# OpenC4D_Shield-version2.net
KiCad netlist of a schematic drawn in EAGLE
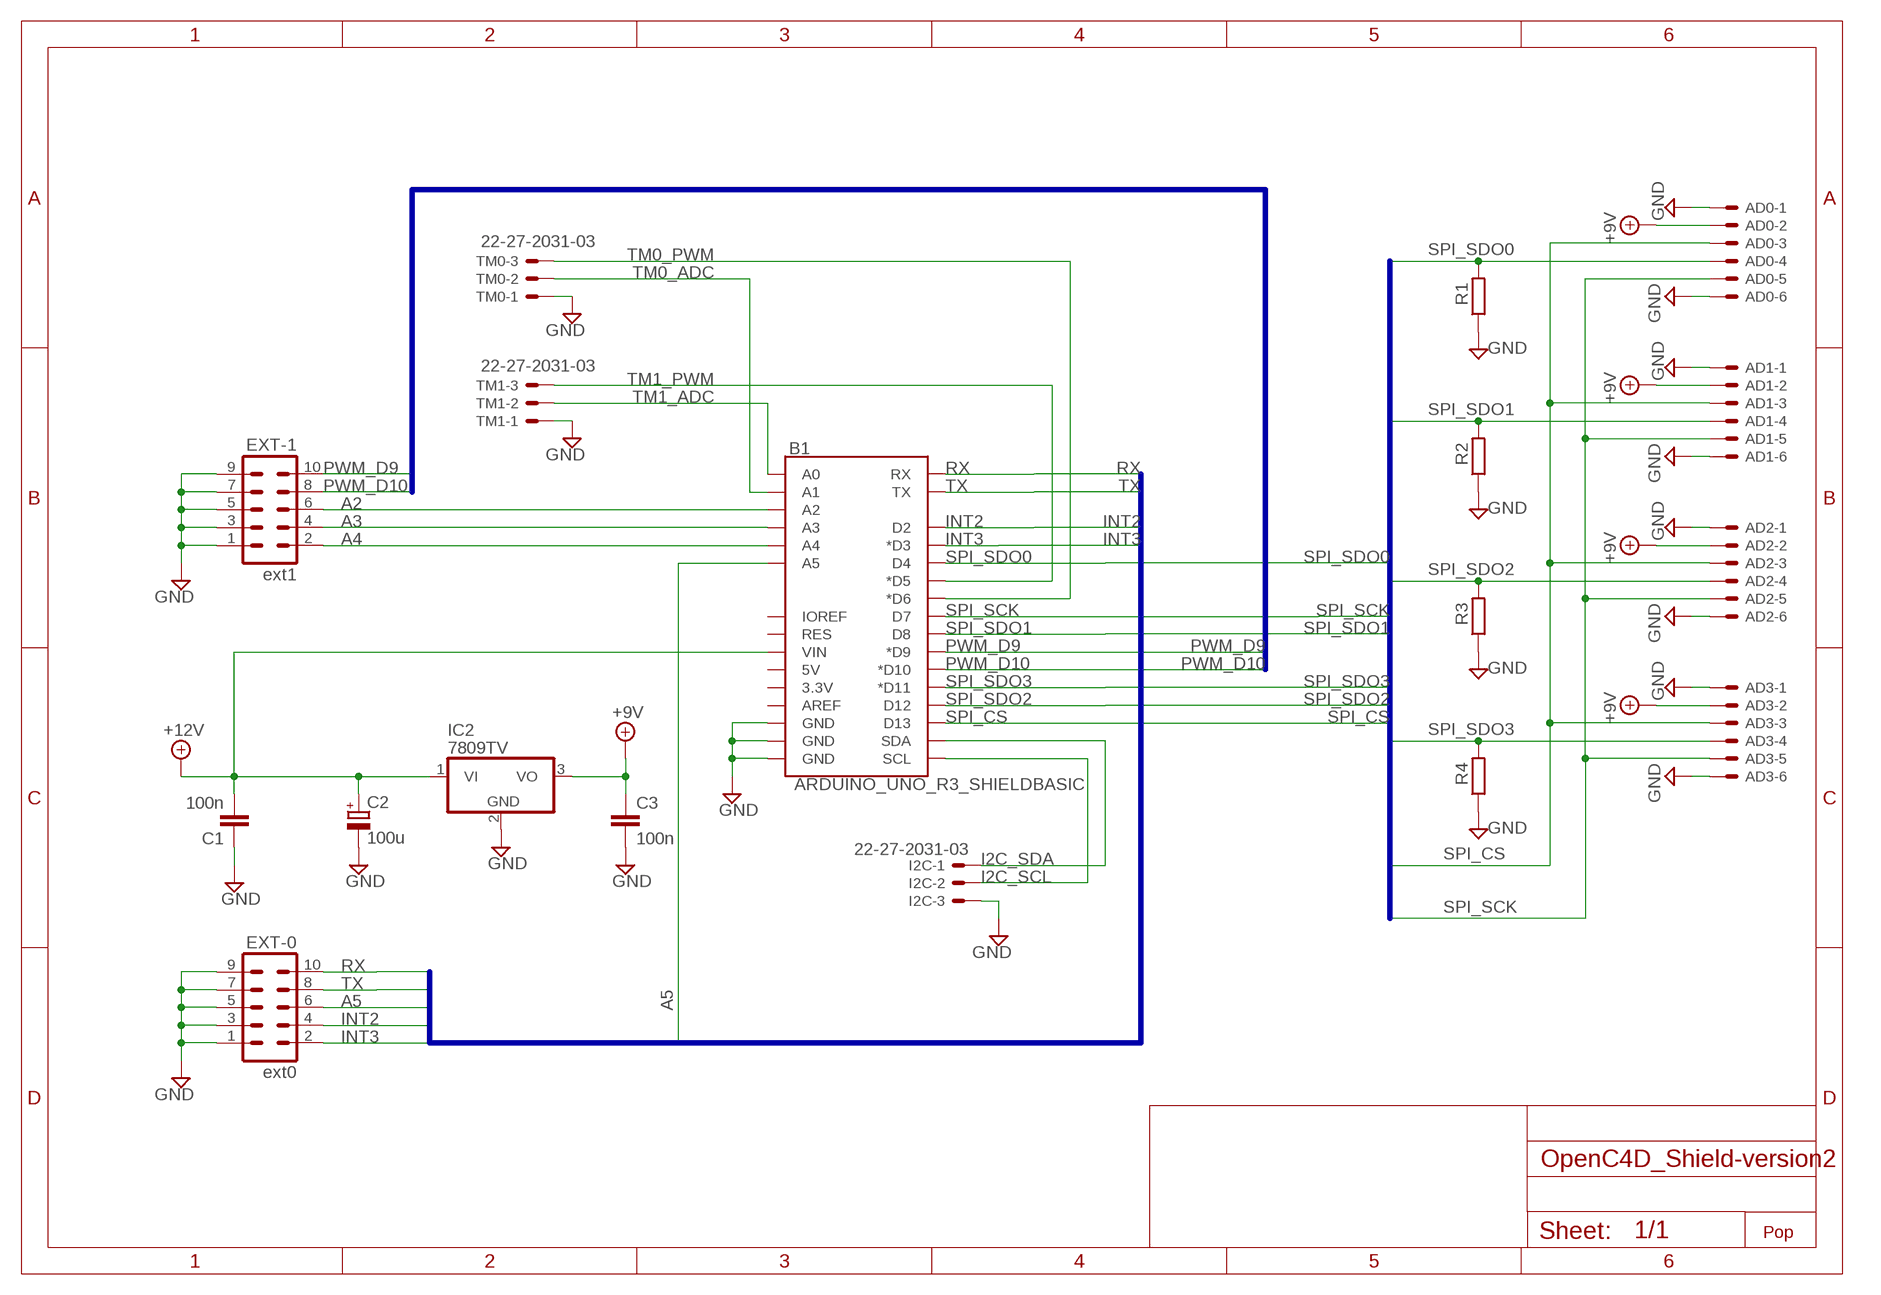
[diagram p0: schematic, sheet 1]

(export (version "E")
  (design (tool "Eeschema 10.0.6"))
  (components
    (comp (ref "AD0")
      (value "22-27-2061-06")
      (footprint "eagle-import:6410-06")
      (libsource (lib "eagle-import") (part "22-?-0627-2061"))
    )
    (comp (ref "AD1")
      (value "22-27-2061-06")
      (footprint "eagle-import:6410-06")
      (libsource (lib "eagle-import") (part "22-?-0627-2061"))
    )
    (comp (ref "AD2")
      (value "22-27-2061-06")
      (footprint "eagle-import:6410-06")
      (libsource (lib "eagle-import") (part "22-?-0627-2061"))
    )
    (comp (ref "AD3")
      (value "22-27-2061-06")
      (footprint "eagle-import:6410-06")
      (libsource (lib "eagle-import") (part "22-?-0627-2061"))
    )
    (comp (ref "B1")
      (value "ARDUINO_UNO_R3_SHIELDBASIC")
      (footprint "eagle-import:UNO_R3_SHIELD")
      (fields (field (name "SPICEPREFIX") "X"))
      (libsource (lib "eagle-import") (part "ARDUINO_UNO_R3_SHIELDBASIC"))
    )
    (comp (ref "C1")
      (value "100n")
      (footprint "eagle-import:C050-025X075")
      (libsource (lib "eagle-import") (part "C-EU050-025X075"))
    )
    (comp (ref "C2")
      (value "100u")
      (footprint "eagle-import:E3,5-8")
      (libsource (lib "eagle-import") (part "CPOL-EUE3.5-8"))
    )
    (comp (ref "C3")
      (value "100n")
      (footprint "eagle-import:C050-025X075")
      (libsource (lib "eagle-import") (part "C-EU050-025X075"))
    )
    (comp (ref "EXT-0")
      (value "ext0")
      (footprint "eagle-import:ML10")
      (libsource (lib "eagle-import") (part "ML10"))
    )
    (comp (ref "EXT-1")
      (value "ext1")
      (footprint "eagle-import:ML10")
      (libsource (lib "eagle-import") (part "ML10"))
    )
    (comp (ref "I2C")
      (value "22-27-2031-03")
      (footprint "eagle-import:6410-03")
      (libsource (lib "eagle-import") (part "22-?-0327-2031"))
    )
    (comp (ref "IC2")
      (value "7809TV")
      (footprint "eagle-import:TO220V")
      (libsource (lib "eagle-import") (part "78TV12"))
    )
    (comp (ref "R1")
      (value "R0204/7")
      (footprint "eagle-import:0204_7")
      (libsource (lib "eagle-import") (part "R0204/7"))
    )
    (comp (ref "R2")
      (value "R0204/7")
      (footprint "eagle-import:0204_7")
      (libsource (lib "eagle-import") (part "R0204/7"))
    )
    (comp (ref "R3")
      (value "R0204/7")
      (footprint "eagle-import:0204_7")
      (libsource (lib "eagle-import") (part "R0204/7"))
    )
    (comp (ref "R4")
      (value "R0204/7")
      (footprint "eagle-import:0204_7")
      (libsource (lib "eagle-import") (part "R0204/7"))
    )
    (comp (ref "TM0")
      (value "22-27-2031-03")
      (footprint "eagle-import:6410-03")
      (libsource (lib "eagle-import") (part "22-?-0327-2031"))
    )
    (comp (ref "TM1")
      (value "22-27-2031-03")
      (footprint "eagle-import:6410-03")
      (libsource (lib "eagle-import") (part "22-?-0327-2031"))
    )
  )
  (nets
    (net (code "1") (name "+9V") (class "Default")
      (node (ref "AD0") (pin "2") (pinfunction "S_2") (pintype "passive"))
      (node (ref "AD1") (pin "2") (pinfunction "S_2") (pintype "passive"))
      (node (ref "AD2") (pin "2") (pinfunction "S_2") (pintype "passive"))
      (node (ref "AD3") (pin "2") (pinfunction "S_2") (pintype "passive"))
      (node (ref "C3") (pin "1") (pinfunction "1_1") (pintype "passive"))
      (node (ref "IC2") (pin "3") (pinfunction "VO_3") (pintype "passive"))
    )
    (net (code "2") (name "+12V") (class "Default")
      (node (ref "B1") (pin "VIN") (pinfunction "VIN_VIN") (pintype "bidirectional"))
      (node (ref "C1") (pin "2") (pinfunction "2_2") (pintype "passive"))
      (node (ref "C2") (pin "+") (pinfunction "+_+") (pintype "passive"))
      (node (ref "IC2") (pin "1") (pinfunction "VI_1") (pintype "input"))
    )
    (net (code "3") (name "/A2") (class "Default")
      (node (ref "B1") (pin "A2") (pinfunction "A2_A2") (pintype "bidirectional"))
      (node (ref "EXT-1") (pin "6") (pinfunction "6_6") (pintype "passive"))
    )
    (net (code "4") (name "/A3") (class "Default")
      (node (ref "B1") (pin "A3") (pinfunction "A3_A3") (pintype "bidirectional"))
      (node (ref "EXT-1") (pin "4") (pinfunction "4_4") (pintype "passive"))
    )
    (net (code "5") (name "/A4") (class "Default")
      (node (ref "B1") (pin "A4") (pinfunction "A4_A4") (pintype "bidirectional"))
      (node (ref "EXT-1") (pin "2") (pinfunction "2_2") (pintype "passive"))
    )
    (net (code "6") (name "/A5") (class "Default")
      (node (ref "B1") (pin "A5") (pinfunction "A5_A5") (pintype "bidirectional"))
      (node (ref "EXT-0") (pin "6") (pinfunction "6_6") (pintype "passive"))
    )
    (net (code "7") (name "/I2C_SCL") (class "Default")
      (node (ref "B1") (pin "SCL") (pinfunction "SCL_SCL") (pintype "bidirectional"))
      (node (ref "I2C") (pin "2") (pinfunction "S_2") (pintype "passive"))
    )
    (net (code "8") (name "/I2C_SDA") (class "Default")
      (node (ref "B1") (pin "SDA") (pinfunction "SDA_SDA") (pintype "bidirectional"))
      (node (ref "I2C") (pin "1") (pinfunction "S_1") (pintype "passive"))
    )
    (net (code "9") (name "/INT2") (class "Default")
      (node (ref "B1") (pin "D2") (pinfunction "D2_D2") (pintype "bidirectional"))
      (node (ref "EXT-0") (pin "4") (pinfunction "4_4") (pintype "passive"))
    )
    (net (code "10") (name "/INT3") (class "Default")
      (node (ref "B1") (pin "D3") (pinfunction "*D3_D3") (pintype "bidirectional"))
      (node (ref "EXT-0") (pin "2") (pinfunction "2_2") (pintype "passive"))
    )
    (net (code "11") (name "/PWM_D9") (class "Default")
      (node (ref "B1") (pin "D9") (pinfunction "*D9_D9") (pintype "bidirectional"))
      (node (ref "EXT-1") (pin "10") (pinfunction "10_10") (pintype "passive"))
    )
    (net (code "12") (name "/PWM_D10") (class "Default")
      (node (ref "B1") (pin "D10") (pinfunction "*D10_D10") (pintype "bidirectional"))
      (node (ref "EXT-1") (pin "8") (pinfunction "8_8") (pintype "passive"))
    )
    (net (code "13") (name "/RX") (class "Default")
      (node (ref "B1") (pin "RX") (pinfunction "RX_RX") (pintype "bidirectional"))
      (node (ref "EXT-0") (pin "10") (pinfunction "10_10") (pintype "passive"))
    )
    (net (code "14") (name "/SPI_CS") (class "Default")
      (node (ref "AD0") (pin "3") (pinfunction "S_3") (pintype "passive"))
      (node (ref "AD1") (pin "3") (pinfunction "S_3") (pintype "passive"))
      (node (ref "AD2") (pin "3") (pinfunction "S_3") (pintype "passive"))
      (node (ref "AD3") (pin "3") (pinfunction "S_3") (pintype "passive"))
      (node (ref "B1") (pin "D13") (pinfunction "D13_D13") (pintype "bidirectional"))
    )
    (net (code "15") (name "/SPI_SCK") (class "Default")
      (node (ref "AD0") (pin "5") (pinfunction "S_5") (pintype "passive"))
      (node (ref "AD1") (pin "5") (pinfunction "S_5") (pintype "passive"))
      (node (ref "AD2") (pin "5") (pinfunction "S_5") (pintype "passive"))
      (node (ref "AD3") (pin "5") (pinfunction "S_5") (pintype "passive"))
      (node (ref "B1") (pin "D7") (pinfunction "D7_D7") (pintype "bidirectional"))
    )
    (net (code "16") (name "/SPI_SDO0") (class "Default")
      (node (ref "AD0") (pin "4") (pinfunction "S_4") (pintype "passive"))
      (node (ref "B1") (pin "D4") (pinfunction "D4_D4") (pintype "bidirectional"))
      (node (ref "R1") (pin "2") (pinfunction "2_2") (pintype "passive"))
    )
    (net (code "17") (name "/SPI_SDO1") (class "Default")
      (node (ref "AD1") (pin "4") (pinfunction "S_4") (pintype "passive"))
      (node (ref "B1") (pin "D8") (pinfunction "D8_D8") (pintype "bidirectional"))
      (node (ref "R2") (pin "2") (pinfunction "2_2") (pintype "passive"))
    )
    (net (code "18") (name "/SPI_SDO2") (class "Default")
      (node (ref "AD2") (pin "4") (pinfunction "S_4") (pintype "passive"))
      (node (ref "B1") (pin "D12") (pinfunction "D12_D12") (pintype "bidirectional"))
      (node (ref "R3") (pin "2") (pinfunction "2_2") (pintype "passive"))
    )
    (net (code "19") (name "/SPI_SDO3") (class "Default")
      (node (ref "AD3") (pin "4") (pinfunction "S_4") (pintype "passive"))
      (node (ref "B1") (pin "D11") (pinfunction "*D11_D11") (pintype "bidirectional"))
      (node (ref "R4") (pin "2") (pinfunction "2_2") (pintype "passive"))
    )
    (net (code "20") (name "/TM0_ADC") (class "Default")
      (node (ref "B1") (pin "A1") (pinfunction "A1_A1") (pintype "bidirectional"))
      (node (ref "TM0") (pin "2") (pinfunction "S_2") (pintype "passive"))
    )
    (net (code "21") (name "/TM0_PWM") (class "Default")
      (node (ref "B1") (pin "D6") (pinfunction "*D6_D6") (pintype "bidirectional"))
      (node (ref "TM0") (pin "3") (pinfunction "S_3") (pintype "passive"))
    )
    (net (code "22") (name "/TM1_ADC") (class "Default")
      (node (ref "B1") (pin "A0") (pinfunction "A0_A0") (pintype "bidirectional"))
      (node (ref "TM1") (pin "2") (pinfunction "S_2") (pintype "passive"))
    )
    (net (code "23") (name "/TM1_PWM") (class "Default")
      (node (ref "B1") (pin "D5") (pinfunction "*D5_D5") (pintype "bidirectional"))
      (node (ref "TM1") (pin "3") (pinfunction "S_3") (pintype "passive"))
    )
    (net (code "24") (name "/TX") (class "Default")
      (node (ref "B1") (pin "TX") (pinfunction "TX_TX") (pintype "bidirectional"))
      (node (ref "EXT-0") (pin "8") (pinfunction "8_8") (pintype "passive"))
    )
    (net (code "25") (name "GND") (class "Default")
      (node (ref "AD0") (pin "1") (pinfunction "S_1") (pintype "passive"))
      (node (ref "AD0") (pin "6") (pinfunction "S_6") (pintype "passive"))
      (node (ref "AD1") (pin "1") (pinfunction "S_1") (pintype "passive"))
      (node (ref "AD1") (pin "6") (pinfunction "S_6") (pintype "passive"))
      (node (ref "AD2") (pin "1") (pinfunction "S_1") (pintype "passive"))
      (node (ref "AD2") (pin "6") (pinfunction "S_6") (pintype "passive"))
      (node (ref "AD3") (pin "1") (pinfunction "S_1") (pintype "passive"))
      (node (ref "AD3") (pin "6") (pinfunction "S_6") (pintype "passive"))
      (node (ref "B1") (pin "GND@0") (pinfunction "GND_GND@0") (pintype "bidirectional"))
      (node (ref "B1") (pin "GND@1") (pinfunction "GND_GND@1") (pintype "bidirectional"))
      (node (ref "B1") (pin "GND@2") (pinfunction "GND_GND@2") (pintype "bidirectional"))
      (node (ref "C1") (pin "1") (pinfunction "1_1") (pintype "passive"))
      (node (ref "C2") (pin "-") (pinfunction "-_-") (pintype "passive"))
      (node (ref "C3") (pin "2") (pinfunction "2_2") (pintype "passive"))
      (node (ref "EXT-0") (pin "1") (pinfunction "1_1") (pintype "passive"))
      (node (ref "EXT-0") (pin "3") (pinfunction "3_3") (pintype "passive"))
      (node (ref "EXT-0") (pin "5") (pinfunction "5_5") (pintype "passive"))
      (node (ref "EXT-0") (pin "7") (pinfunction "7_7") (pintype "passive"))
      (node (ref "EXT-0") (pin "9") (pinfunction "9_9") (pintype "passive"))
      (node (ref "EXT-1") (pin "1") (pinfunction "1_1") (pintype "passive"))
      (node (ref "EXT-1") (pin "3") (pinfunction "3_3") (pintype "passive"))
      (node (ref "EXT-1") (pin "5") (pinfunction "5_5") (pintype "passive"))
      (node (ref "EXT-1") (pin "7") (pinfunction "7_7") (pintype "passive"))
      (node (ref "EXT-1") (pin "9") (pinfunction "9_9") (pintype "passive"))
      (node (ref "I2C") (pin "3") (pinfunction "S_3") (pintype "passive"))
      (node (ref "IC2") (pin "2") (pinfunction "GND_2") (pintype "passive"))
      (node (ref "R1") (pin "1") (pinfunction "1_1") (pintype "passive"))
      (node (ref "R2") (pin "1") (pinfunction "1_1") (pintype "passive"))
      (node (ref "R3") (pin "1") (pinfunction "1_1") (pintype "passive"))
      (node (ref "R4") (pin "1") (pinfunction "1_1") (pintype "passive"))
      (node (ref "TM0") (pin "1") (pinfunction "S_1") (pintype "passive"))
      (node (ref "TM1") (pin "1") (pinfunction "S_1") (pintype "passive"))
    )
    (net (code "26") (name "unconnected-(B1-Pad3.3V)") (class "Default")
      (node (ref "B1") (pin "3.3V") (pinfunction "3.3V_3.3V") (pintype "bidirectional"))
    )
    (net (code "27") (name "unconnected-(B1-Pad5V)") (class "Default")
      (node (ref "B1") (pin "5V") (pinfunction "5V_5V") (pintype "bidirectional"))
    )
    (net (code "28") (name "unconnected-(B1-PadAREF)") (class "Default")
      (node (ref "B1") (pin "AREF") (pinfunction "AREF_AREF") (pintype "bidirectional"))
    )
    (net (code "29") (name "unconnected-(B1-PadIOREF)") (class "Default")
      (node (ref "B1") (pin "IOREF") (pinfunction "IOREF_IOREF") (pintype "bidirectional"))
    )
    (net (code "30") (name "unconnected-(B1-PadRES)") (class "Default")
      (node (ref "B1") (pin "RES") (pinfunction "RES_RES") (pintype "bidirectional"))
    )
  )
)
